# STM32Schemetics.net
KiCad netlist of a schematic drawn in Altium Designer
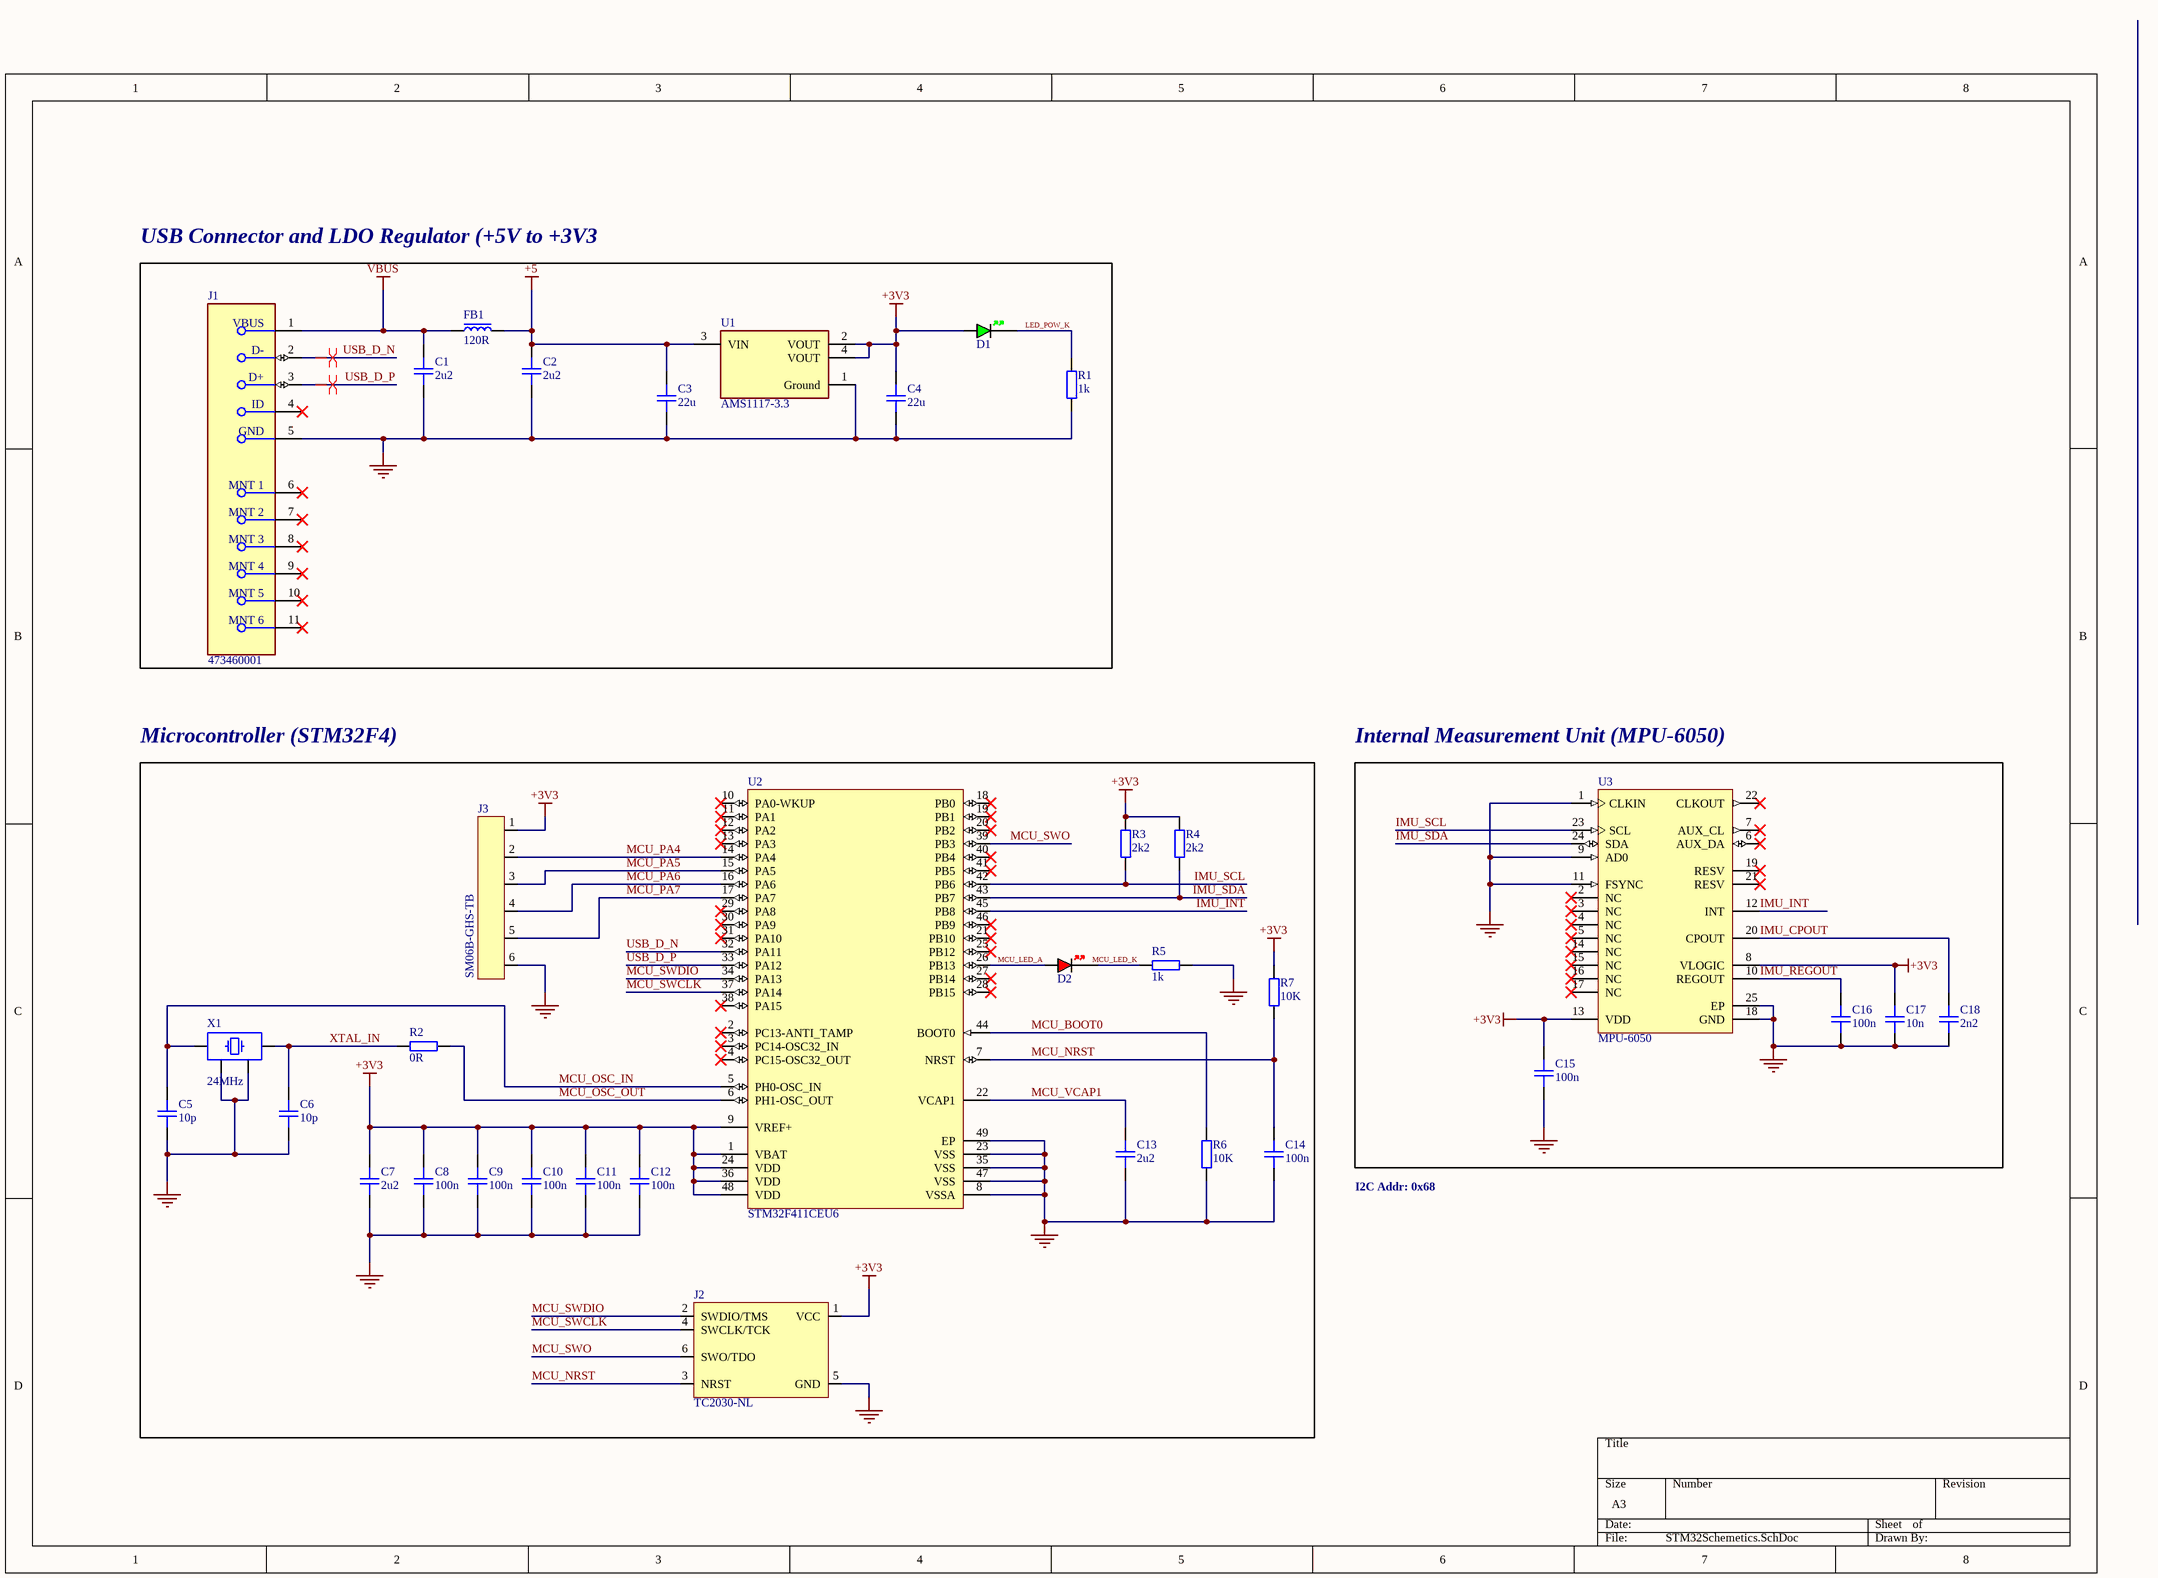
[diagram p0: STM32Schemetics.SchDoc]

(export (version "E")
  (design (tool "Eeschema 10.0.6"))
  (components
    (comp (ref "C1")
      (value "2u2")
      (footprint "CAP_0402")
      (description "Capacitor SMD 0402")
      (libsource (lib "Schematic-Lib-PhilsLab") (part "CAP_0402"))
    )
    (comp (ref "C2")
      (value "2u2")
      (footprint "CAP_0402")
      (description "Capacitor SMD 0402")
      (libsource (lib "Schematic-Lib-PhilsLab") (part "CAP_0402"))
    )
    (comp (ref "C3")
      (value "22u")
      (footprint "CAP_0805")
      (description "Capacitor SMD 0805")
      (libsource (lib "Schematic-Lib-PhilsLab") (part "CAP_0805"))
    )
    (comp (ref "C4")
      (value "22u")
      (footprint "CAP_0805")
      (description "Capacitor SMD 0805")
      (libsource (lib "Schematic-Lib-PhilsLab") (part "CAP_0805"))
    )
    (comp (ref "C5")
      (value "10p")
      (footprint "CAP_0402")
      (description "Capacitor SMD 0402")
      (libsource (lib "Schematic-Lib-PhilsLab") (part "CAP_0402"))
    )
    (comp (ref "C6")
      (value "10p")
      (footprint "CAP_0402")
      (description "Capacitor SMD 0402")
      (libsource (lib "Schematic-Lib-PhilsLab") (part "CAP_0402"))
    )
    (comp (ref "C7")
      (value "2u2")
      (footprint "CAP_0603")
      (description "Capacitor SMD 0603")
      (libsource (lib "Schematic-Lib-PhilsLab") (part "CAP_0603"))
    )
    (comp (ref "C8")
      (value "100n")
      (footprint "CAP_0402")
      (description "Capacitor SMD 0402")
      (libsource (lib "Schematic-Lib-PhilsLab") (part "CAP_0402"))
    )
    (comp (ref "C9")
      (value "100n")
      (footprint "CAP_0402")
      (description "Capacitor SMD 0402")
      (libsource (lib "Schematic-Lib-PhilsLab") (part "CAP_0402"))
    )
    (comp (ref "C10")
      (value "100n")
      (footprint "CAP_0402")
      (description "Capacitor SMD 0402")
      (libsource (lib "Schematic-Lib-PhilsLab") (part "CAP_0402"))
    )
    (comp (ref "C11")
      (value "100n")
      (footprint "CAP_0402")
      (description "Capacitor SMD 0402")
      (libsource (lib "Schematic-Lib-PhilsLab") (part "CAP_0402"))
    )
    (comp (ref "C12")
      (value "100n")
      (footprint "CAP_0402")
      (description "Capacitor SMD 0402")
      (libsource (lib "Schematic-Lib-PhilsLab") (part "CAP_0402"))
    )
    (comp (ref "C13")
      (value "2u2")
      (footprint "CAP_0603")
      (description "Capacitor SMD 0603")
      (libsource (lib "Schematic-Lib-PhilsLab") (part "CAP_0603"))
    )
    (comp (ref "C14")
      (value "100n")
      (footprint "CAP_0402")
      (description "Capacitor SMD 0402")
      (libsource (lib "Schematic-Lib-PhilsLab") (part "CAP_0402"))
    )
    (comp (ref "C15")
      (value "100n")
      (footprint "CAP_0402")
      (description "Capacitor SMD 0402")
      (libsource (lib "Schematic-Lib-PhilsLab") (part "CAP_0402"))
    )
    (comp (ref "C16")
      (value "100n")
      (footprint "CAP_0402")
      (description "Capacitor SMD 0402")
      (libsource (lib "Schematic-Lib-PhilsLab") (part "CAP_0402"))
    )
    (comp (ref "C17")
      (value "10n")
      (footprint "CAP_0402")
      (description "Capacitor SMD 0402")
      (libsource (lib "Schematic-Lib-PhilsLab") (part "CAP_0402"))
    )
    (comp (ref "C18")
      (value "2n2")
      (footprint "CAP_0402")
      (description "Capacitor SMD 0402")
      (libsource (lib "Schematic-Lib-PhilsLab") (part "CAP_0402"))
    )
    (comp (ref "D1")
      (value "GREEN")
      (footprint "LED_0402_GREEN")
      (description "LED 0402 GREEN SMD")
      (libsource (lib "Schematic-Lib-PhilsLab") (part "LED_0402_GREEN"))
    )
    (comp (ref "D2")
      (value "RED")
      (footprint "LED_0402_RED")
      (description "LED 0402 RED SMD")
      (libsource (lib "Schematic-Lib-PhilsLab") (part "LED_0402_RED"))
    )
    (comp (ref "FB1")
      (value "120R")
      (footprint "FB_0603")
      (description "Ferrite Bead SMD 0603")
      (libsource (lib "Schematic-Lib-PhilsLab") (part "FB_0603"))
    )
    (comp (ref "J1")
      (value "473460001")
      (footprint "FP-473460001-MFG")
      (description "CONN RCPT USB2.0 MICRO B SMD R/A")
      (fields
        (field (name "OCTOPART") "https://octopart.com/47346-0001-molex-7164928")
        (field (name "MANUFACTURER") "Molex")
      )
      (libsource (lib "Altium Content Vault") (part "53ae1f1d9b557310b43ca686e5bb76a"))
    )
    (comp (ref "J2")
      (value "TC2030-NL")
      (footprint "TC2030-NL-FP")
      (description "Tag-Connect No-Solder SWD Debug Connector (No Legs) DO NOT PLACE")
      (fields
        (field (name "MANUFACTURER") "Tag-Connect")
        (field (name "MANUFACTURER PART NUMBER") "TC2030-NL-FP")
      )
      (libsource (lib "Schematic-Lib-PhilsLab") (part "TC2030-NL"))
    )
    (comp (ref "J3")
      (value "SM06B-GHS-TB")
      (footprint "SM06B-GHS-TB")
      (description "Header Connector 6 Position 1.25MM Pitch SMD Horizontal JST GH")
      (fields (field (name "MANUFACTURER") "JST"))
      (libsource (lib "Schematic-Lib-PhilsLab") (part "SM06B-GHS-TB"))
    )
    (comp (ref "R1")
      (value "1k")
      (footprint "RES_0402")
      (description "Resistor SMD 0402")
      (libsource (lib "Schematic-Lib-PhilsLab") (part "RES_0402"))
    )
    (comp (ref "R2")
      (value "0R")
      (footprint "RES_0402")
      (description "Resistor SMD 0402")
      (libsource (lib "Schematic-Lib-PhilsLab") (part "RES_0402"))
    )
    (comp (ref "R3")
      (value "2k2")
      (footprint "RES_0402")
      (description "Resistor SMD 0402")
      (libsource (lib "Schematic-Lib-PhilsLab") (part "RES_0402"))
    )
    (comp (ref "R4")
      (value "2k2")
      (footprint "RES_0402")
      (description "Resistor SMD 0402")
      (libsource (lib "Schematic-Lib-PhilsLab") (part "RES_0402"))
    )
    (comp (ref "R5")
      (value "1k")
      (footprint "RES_0402")
      (description "Resistor SMD 0402")
      (libsource (lib "Schematic-Lib-PhilsLab") (part "RES_0402"))
    )
    (comp (ref "R6")
      (value "10K")
      (footprint "RES_0402")
      (description "Resistor SMD 0402")
      (libsource (lib "Schematic-Lib-PhilsLab") (part "RES_0402"))
    )
    (comp (ref "R7")
      (value "10K")
      (footprint "RES_0402")
      (description "Resistor SMD 0402")
      (libsource (lib "Schematic-Lib-PhilsLab") (part "RES_0402"))
    )
    (comp (ref "U1")
      (value "AMS1117-3.3")
      (footprint "FP-AMS1117-IPC_C")
      (description "LDO Voltage Regulators 1A, 3.3V")
      (fields
        (field (name "OCTOPART") "https://octopart.com/ams1117-3.3-advanced+monolithic+systems-25899300")
        (field (name "MANUFACTURER") "Advanced Monolithic Systems")
      )
      (libsource (lib "Altium Content Vault") (part "8bdbb5f8e77002000e30dd2845d0354"))
    )
    (comp (ref "U2")
      (value "STM32F411CEU6")
      (footprint "STM-UFQFPN48_L")
      (libsource (lib "Altium Content Vault") (part "MC-ARM-STM32F411-UFQFPN48"))
    )
    (comp (ref "U3")
      (value "MPU-6050")
      (footprint "IS-QFN-24_V")
      (fields (field (name "MANUFACTURER") "InvenSense"))
      (libsource (lib "Altium Content Vault") (part "IS-MPU-6050-QFN-24"))
    )
    (comp (ref "X1")
      (value "24MHz")
      (footprint "XTAL_3225")
      (description "Crystal SMD 24MHz 10PPM 7pF 3225")
      (fields
        (field (name "MANUFACTURER") "Epson")
        (field (name "MANUFACTURER PART NUMBER") "TSX-3225 24.0000MF15X-AC")
      )
      (libsource (lib "Schematic-Lib-PhilsLab") (part "TSX-3225_24.0000MF15X-AC"))
    )
  )
  (nets
    (net (code "1") (name "+3V3") (class "Default")
      (node (ref "C10") (pin "2") (pinfunction "2_2") (pintype "passive"))
      (node (ref "C11") (pin "2") (pinfunction "2_2") (pintype "passive"))
      (node (ref "C12") (pin "2") (pinfunction "2_2") (pintype "passive"))
      (node (ref "C15") (pin "2") (pinfunction "2_2") (pintype "passive"))
      (node (ref "C17") (pin "2") (pinfunction "2_2") (pintype "passive"))
      (node (ref "C4") (pin "2") (pinfunction "2_2") (pintype "passive"))
      (node (ref "C7") (pin "2") (pinfunction "2_2") (pintype "passive"))
      (node (ref "C8") (pin "2") (pinfunction "2_2") (pintype "passive"))
      (node (ref "C9") (pin "2") (pinfunction "2_2") (pintype "passive"))
      (node (ref "D1") (pin "A") (pinfunction "A_A") (pintype "passive"))
      (node (ref "J2") (pin "1") (pinfunction "VCC_1") (pintype "passive"))
      (node (ref "J3") (pin "1") (pinfunction "1_1") (pintype "passive"))
      (node (ref "R3") (pin "2") (pinfunction "2_2") (pintype "passive"))
      (node (ref "R4") (pin "2") (pinfunction "2_2") (pintype "passive"))
      (node (ref "R7") (pin "2") (pinfunction "2_2") (pintype "passive"))
      (node (ref "U1") (pin "2") (pinfunction "VOUT_2") (pintype "passive"))
      (node (ref "U1") (pin "4") (pinfunction "VOUT_4") (pintype "passive"))
      (node (ref "U2") (pin "1") (pinfunction "VBAT_1") (pintype "power_in"))
      (node (ref "U2") (pin "24") (pinfunction "VDD_24") (pintype "power_in"))
      (node (ref "U2") (pin "36") (pinfunction "VDD_36") (pintype "power_in"))
      (node (ref "U2") (pin "48") (pinfunction "VDD_48") (pintype "power_in"))
      (node (ref "U2") (pin "9") (pinfunction "VREF+_9") (pintype "power_in"))
      (node (ref "U3") (pin "13") (pinfunction "VDD_13") (pintype "power_in"))
      (node (ref "U3") (pin "8") (pinfunction "VLOGIC_8") (pintype "power_in"))
    )
    (net (code "2") (name "+5") (class "Default")
      (node (ref "C2") (pin "2") (pinfunction "2_2") (pintype "passive"))
      (node (ref "C3") (pin "2") (pinfunction "2_2") (pintype "passive"))
      (node (ref "FB1") (pin "2") (pinfunction "2_2") (pintype "passive"))
      (node (ref "U1") (pin "3") (pinfunction "VIN_3") (pintype "power_in"))
    )
    (net (code "3") (name "/IMU_CPOUT") (class "Default")
      (node (ref "C18") (pin "2") (pinfunction "2_2") (pintype "passive"))
      (node (ref "U3") (pin "20") (pinfunction "CPOUT_20") (pintype "passive"))
    )
    (net (code "4") (name "/IMU_INT") (class "Default")
      (node (ref "U2") (pin "45") (pinfunction "PB8_45") (pintype "bidirectional"))
      (node (ref "U3") (pin "12") (pinfunction "INT_12") (pintype "open_collector"))
    )
    (net (code "5") (name "/IMU_REGOUT") (class "Default")
      (node (ref "C16") (pin "2") (pinfunction "2_2") (pintype "passive"))
      (node (ref "U3") (pin "10") (pinfunction "REGOUT_10") (pintype "passive"))
    )
    (net (code "6") (name "/IMU_SCL") (class "Default")
      (node (ref "R3") (pin "1") (pinfunction "1_1") (pintype "passive"))
      (node (ref "U2") (pin "42") (pinfunction "PB6_42") (pintype "bidirectional"))
      (node (ref "U3") (pin "23") (pinfunction "SCL_23") (pintype "input"))
    )
    (net (code "7") (name "/IMU_SDA") (class "Default")
      (node (ref "R4") (pin "1") (pinfunction "1_1") (pintype "passive"))
      (node (ref "U2") (pin "43") (pinfunction "PB7_43") (pintype "bidirectional"))
      (node (ref "U3") (pin "24") (pinfunction "SDA_24") (pintype "bidirectional"))
    )
    (net (code "8") (name "/LED_POW_K") (class "Default")
      (node (ref "D1") (pin "K") (pinfunction "K_K") (pintype "passive"))
      (node (ref "R1") (pin "2") (pinfunction "2_2") (pintype "passive"))
    )
    (net (code "9") (name "/MCU_BOOT0") (class "Default")
      (node (ref "R6") (pin "2") (pinfunction "2_2") (pintype "passive"))
      (node (ref "U2") (pin "44") (pinfunction "BOOT0_44") (pintype "input"))
    )
    (net (code "10") (name "/MCU_LED_A") (class "Default")
      (node (ref "D2") (pin "A") (pinfunction "A_A") (pintype "passive"))
      (node (ref "U2") (pin "26") (pinfunction "PB13_26") (pintype "bidirectional"))
    )
    (net (code "11") (name "/MCU_LED_K") (class "Default")
      (node (ref "D2") (pin "K") (pinfunction "K_K") (pintype "passive"))
      (node (ref "R5") (pin "2") (pinfunction "2_2") (pintype "passive"))
    )
    (net (code "12") (name "/MCU_NRST") (class "Default")
      (node (ref "C14") (pin "2") (pinfunction "2_2") (pintype "passive"))
      (node (ref "J2") (pin "3") (pinfunction "NRST_3") (pintype "passive"))
      (node (ref "R7") (pin "1") (pinfunction "1_1") (pintype "passive"))
      (node (ref "U2") (pin "7") (pinfunction "NRST_7") (pintype "bidirectional"))
    )
    (net (code "13") (name "/MCU_OSC_IN") (class "Default")
      (node (ref "C5") (pin "2") (pinfunction "2_2") (pintype "passive"))
      (node (ref "U2") (pin "5") (pinfunction "PH0-OSC_IN_5") (pintype "bidirectional"))
      (node (ref "X1") (pin "1") (pinfunction "1_1") (pintype "passive"))
    )
    (net (code "14") (name "/MCU_OSC_OUT") (class "Default")
      (node (ref "R2") (pin "1") (pinfunction "1_1") (pintype "passive"))
      (node (ref "U2") (pin "6") (pinfunction "PH1-OSC_OUT_6") (pintype "bidirectional"))
    )
    (net (code "15") (name "/MCU_PA4") (class "Default")
      (node (ref "J3") (pin "2") (pinfunction "2_2") (pintype "passive"))
      (node (ref "U2") (pin "14") (pinfunction "PA4_14") (pintype "bidirectional"))
    )
    (net (code "16") (name "/MCU_PA5") (class "Default")
      (node (ref "J3") (pin "3") (pinfunction "3_3") (pintype "passive"))
      (node (ref "U2") (pin "15") (pinfunction "PA5_15") (pintype "bidirectional"))
    )
    (net (code "17") (name "/MCU_PA6") (class "Default")
      (node (ref "J3") (pin "4") (pinfunction "4_4") (pintype "passive"))
      (node (ref "U2") (pin "16") (pinfunction "PA6_16") (pintype "bidirectional"))
    )
    (net (code "18") (name "/MCU_PA7") (class "Default")
      (node (ref "J3") (pin "5") (pinfunction "5_5") (pintype "passive"))
      (node (ref "U2") (pin "17") (pinfunction "PA7_17") (pintype "bidirectional"))
    )
    (net (code "19") (name "/MCU_SWCLK") (class "Default")
      (node (ref "J2") (pin "4") (pinfunction "SWCLK/TCK_4") (pintype "passive"))
      (node (ref "U2") (pin "37") (pinfunction "PA14_37") (pintype "bidirectional"))
    )
    (net (code "20") (name "/MCU_SWDIO") (class "Default")
      (node (ref "J2") (pin "2") (pinfunction "SWDIO/TMS_2") (pintype "passive"))
      (node (ref "U2") (pin "34") (pinfunction "PA13_34") (pintype "bidirectional"))
    )
    (net (code "21") (name "/MCU_SWO") (class "Default")
      (node (ref "J2") (pin "6") (pinfunction "SWO/TDO_6") (pintype "passive"))
      (node (ref "U2") (pin "39") (pinfunction "PB3_39") (pintype "bidirectional"))
    )
    (net (code "22") (name "/MCU_VCAP1") (class "Default")
      (node (ref "C13") (pin "2") (pinfunction "2_2") (pintype "passive"))
      (node (ref "U2") (pin "22") (pinfunction "VCAP1_22") (pintype "passive"))
    )
    (net (code "23") (name "/USB_D_N") (class "Default")
      (node (ref "J1") (pin "2") (pinfunction "D-_2") (pintype "bidirectional"))
      (node (ref "U2") (pin "32") (pinfunction "PA11_32") (pintype "bidirectional"))
    )
    (net (code "24") (name "/USB_D_P") (class "Default")
      (node (ref "J1") (pin "3") (pinfunction "D+_3") (pintype "bidirectional"))
      (node (ref "U2") (pin "33") (pinfunction "PA12_33") (pintype "bidirectional"))
    )
    (net (code "25") (name "/XTAL_IN") (class "Default")
      (node (ref "C6") (pin "2") (pinfunction "2_2") (pintype "passive"))
      (node (ref "R2") (pin "2") (pinfunction "2_2") (pintype "passive"))
      (node (ref "X1") (pin "3") (pinfunction "3_3") (pintype "passive"))
    )
    (net (code "26") (name "GND") (class "Default")
      (node (ref "C1") (pin "1") (pinfunction "1_1") (pintype "passive"))
      (node (ref "C10") (pin "1") (pinfunction "1_1") (pintype "passive"))
      (node (ref "C11") (pin "1") (pinfunction "1_1") (pintype "passive"))
      (node (ref "C12") (pin "1") (pinfunction "1_1") (pintype "passive"))
      (node (ref "C13") (pin "1") (pinfunction "1_1") (pintype "passive"))
      (node (ref "C14") (pin "1") (pinfunction "1_1") (pintype "passive"))
      (node (ref "C15") (pin "1") (pinfunction "1_1") (pintype "passive"))
      (node (ref "C16") (pin "1") (pinfunction "1_1") (pintype "passive"))
      (node (ref "C17") (pin "1") (pinfunction "1_1") (pintype "passive"))
      (node (ref "C18") (pin "1") (pinfunction "1_1") (pintype "passive"))
      (node (ref "C2") (pin "1") (pinfunction "1_1") (pintype "passive"))
      (node (ref "C3") (pin "1") (pinfunction "1_1") (pintype "passive"))
      (node (ref "C4") (pin "1") (pinfunction "1_1") (pintype "passive"))
      (node (ref "C5") (pin "1") (pinfunction "1_1") (pintype "passive"))
      (node (ref "C6") (pin "1") (pinfunction "1_1") (pintype "passive"))
      (node (ref "C7") (pin "1") (pinfunction "1_1") (pintype "passive"))
      (node (ref "C8") (pin "1") (pinfunction "1_1") (pintype "passive"))
      (node (ref "C9") (pin "1") (pinfunction "1_1") (pintype "passive"))
      (node (ref "J1") (pin "5") (pinfunction "GND_5") (pintype "power_in"))
      (node (ref "J2") (pin "5") (pinfunction "GND_5") (pintype "passive"))
      (node (ref "J3") (pin "6") (pinfunction "6_6") (pintype "passive"))
      (node (ref "R1") (pin "1") (pinfunction "1_1") (pintype "passive"))
      (node (ref "R5") (pin "1") (pinfunction "1_1") (pintype "passive"))
      (node (ref "R6") (pin "1") (pinfunction "1_1") (pintype "passive"))
      (node (ref "U1") (pin "1") (pinfunction "Ground_1") (pintype "power_in"))
      (node (ref "U2") (pin "23") (pinfunction "VSS_23") (pintype "power_in"))
      (node (ref "U2") (pin "35") (pinfunction "VSS_35") (pintype "power_in"))
      (node (ref "U2") (pin "47") (pinfunction "VSS_47") (pintype "power_in"))
      (node (ref "U2") (pin "49") (pinfunction "EP_49") (pintype "power_in"))
      (node (ref "U2") (pin "8") (pinfunction "VSSA_8") (pintype "power_in"))
      (node (ref "U3") (pin "1") (pinfunction "CLKIN_1") (pintype "input"))
      (node (ref "U3") (pin "11") (pinfunction "FSYNC_11") (pintype "input"))
      (node (ref "U3") (pin "18") (pinfunction "GND_18") (pintype "power_in"))
      (node (ref "U3") (pin "25") (pinfunction "EP_25") (pintype "power_in"))
      (node (ref "U3") (pin "9") (pinfunction "AD0_9") (pintype "input"))
      (node (ref "X1") (pin "2") (pinfunction "2_2") (pintype "passive"))
      (node (ref "X1") (pin "4") (pinfunction "4_4") (pintype "passive"))
    )
    (net (code "27") (name "VBUS") (class "Default")
      (node (ref "C1") (pin "2") (pinfunction "2_2") (pintype "passive"))
      (node (ref "FB1") (pin "1") (pinfunction "1_1") (pintype "passive"))
      (node (ref "J1") (pin "1") (pinfunction "VBUS_1") (pintype "power_in"))
    )
    (net (code "28") (name "unconnected-(J1-ID-Pad4)") (class "Default")
      (node (ref "J1") (pin "4") (pinfunction "ID_4") (pintype "passive+no_connect"))
    )
    (net (code "29") (name "unconnected-(J1-MNT_1-Pad6)") (class "Default")
      (node (ref "J1") (pin "6") (pinfunction "MNT_1_6") (pintype "passive+no_connect"))
    )
    (net (code "30") (name "unconnected-(J1-MNT_2-Pad7)") (class "Default")
      (node (ref "J1") (pin "7") (pinfunction "MNT_2_7") (pintype "passive+no_connect"))
    )
    (net (code "31") (name "unconnected-(J1-MNT_3-Pad8)") (class "Default")
      (node (ref "J1") (pin "8") (pinfunction "MNT_3_8") (pintype "passive+no_connect"))
    )
    (net (code "32") (name "unconnected-(J1-MNT_4-Pad9)") (class "Default")
      (node (ref "J1") (pin "9") (pinfunction "MNT_4_9") (pintype "passive+no_connect"))
    )
    (net (code "33") (name "unconnected-(J1-MNT_5-Pad10)") (class "Default")
      (node (ref "J1") (pin "10") (pinfunction "MNT_5_10") (pintype "passive+no_connect"))
    )
    (net (code "34") (name "unconnected-(J1-MNT_6-Pad11)") (class "Default")
      (node (ref "J1") (pin "11") (pinfunction "MNT_6_11") (pintype "passive+no_connect"))
    )
    (net (code "35") (name "unconnected-(U2-PA0-WKUP-Pad10)") (class "Default")
      (node (ref "U2") (pin "10") (pinfunction "PA0-WKUP_10") (pintype "bidirectional+no_connect"))
    )
    (net (code "36") (name "unconnected-(U2-PA1-Pad11)") (class "Default")
      (node (ref "U2") (pin "11") (pinfunction "PA1_11") (pintype "bidirectional+no_connect"))
    )
    (net (code "37") (name "unconnected-(U2-PA2-Pad12)") (class "Default")
      (node (ref "U2") (pin "12") (pinfunction "PA2_12") (pintype "bidirectional+no_connect"))
    )
    (net (code "38") (name "unconnected-(U2-PA3-Pad13)") (class "Default")
      (node (ref "U2") (pin "13") (pinfunction "PA3_13") (pintype "bidirectional+no_connect"))
    )
    (net (code "39") (name "unconnected-(U2-PA8-Pad29)") (class "Default")
      (node (ref "U2") (pin "29") (pinfunction "PA8_29") (pintype "bidirectional+no_connect"))
    )
    (net (code "40") (name "unconnected-(U2-PA9-Pad30)") (class "Default")
      (node (ref "U2") (pin "30") (pinfunction "PA9_30") (pintype "bidirectional+no_connect"))
    )
    (net (code "41") (name "unconnected-(U2-PA10-Pad31)") (class "Default")
      (node (ref "U2") (pin "31") (pinfunction "PA10_31") (pintype "bidirectional+no_connect"))
    )
    (net (code "42") (name "unconnected-(U2-PA15-Pad38)") (class "Default")
      (node (ref "U2") (pin "38") (pinfunction "PA15_38") (pintype "bidirectional+no_connect"))
    )
    (net (code "43") (name "unconnected-(U2-PB0-Pad18)") (class "Default")
      (node (ref "U2") (pin "18") (pinfunction "PB0_18") (pintype "bidirectional+no_connect"))
    )
    (net (code "44") (name "unconnected-(U2-PB1-Pad19)") (class "Default")
      (node (ref "U2") (pin "19") (pinfunction "PB1_19") (pintype "bidirectional+no_connect"))
    )
    (net (code "45") (name "unconnected-(U2-PB2-Pad20)") (class "Default")
      (node (ref "U2") (pin "20") (pinfunction "PB2_20") (pintype "bidirectional+no_connect"))
    )
    (net (code "46") (name "unconnected-(U2-PB4-Pad40)") (class "Default")
      (node (ref "U2") (pin "40") (pinfunction "PB4_40") (pintype "bidirectional+no_connect"))
    )
    (net (code "47") (name "unconnected-(U2-PB5-Pad41)") (class "Default")
      (node (ref "U2") (pin "41") (pinfunction "PB5_41") (pintype "bidirectional+no_connect"))
    )
    (net (code "48") (name "unconnected-(U2-PB9-Pad46)") (class "Default")
      (node (ref "U2") (pin "46") (pinfunction "PB9_46") (pintype "bidirectional+no_connect"))
    )
    (net (code "49") (name "unconnected-(U2-PB10-Pad21)") (class "Default")
      (node (ref "U2") (pin "21") (pinfunction "PB10_21") (pintype "bidirectional+no_connect"))
    )
    (net (code "50") (name "unconnected-(U2-PB12-Pad25)") (class "Default")
      (node (ref "U2") (pin "25") (pinfunction "PB12_25") (pintype "bidirectional+no_connect"))
    )
    (net (code "51") (name "unconnected-(U2-PB14-Pad27)") (class "Default")
      (node (ref "U2") (pin "27") (pinfunction "PB14_27") (pintype "bidirectional+no_connect"))
    )
    (net (code "52") (name "unconnected-(U2-PB15-Pad28)") (class "Default")
      (node (ref "U2") (pin "28") (pinfunction "PB15_28") (pintype "bidirectional+no_connect"))
    )
    (net (code "53") (name "unconnected-(U2-PC13-ANTI_TAMP-Pad2)") (class "Default")
      (node (ref "U2") (pin "2") (pinfunction "PC13-ANTI_TAMP_2") (pintype "bidirectional+no_connect"))
    )
    (net (code "54") (name "unconnected-(U2-PC14-OSC32_IN-Pad3)") (class "Default")
      (node (ref "U2") (pin "3") (pinfunction "PC14-OSC32_IN_3") (pintype "bidirectional+no_connect"))
    )
    (net (code "55") (name "unconnected-(U2-PC15-OSC32_OUT-Pad4)") (class "Default")
      (node (ref "U2") (pin "4") (pinfunction "PC15-OSC32_OUT_4") (pintype "bidirectional+no_connect"))
    )
    (net (code "56") (name "unconnected-(U3-AUX_CL-Pad7)") (class "Default")
      (node (ref "U3") (pin "7") (pinfunction "AUX_CL_7") (pintype "output+no_connect"))
    )
    (net (code "57") (name "unconnected-(U3-AUX_DA-Pad6)") (class "Default")
      (node (ref "U3") (pin "6") (pinfunction "AUX_DA_6") (pintype "bidirectional+no_connect"))
    )
    (net (code "58") (name "unconnected-(U3-CLKOUT-Pad22)") (class "Default")
      (node (ref "U3") (pin "22") (pinfunction "CLKOUT_22") (pintype "output+no_connect"))
    )
    (net (code "59") (name "unconnected-(U3-NC-Pad2)") (class "Default")
      (node (ref "U3") (pin "2") (pinfunction "NC_2") (pintype "passive+no_connect"))
    )
    (net (code "60") (name "unconnected-(U3-NC-Pad3)") (class "Default")
      (node (ref "U3") (pin "3") (pinfunction "NC_3") (pintype "passive+no_connect"))
    )
    (net (code "61") (name "unconnected-(U3-NC-Pad4)") (class "Default")
      (node (ref "U3") (pin "4") (pinfunction "NC_4") (pintype "passive+no_connect"))
    )
    (net (code "62") (name "unconnected-(U3-NC-Pad5)") (class "Default")
      (node (ref "U3") (pin "5") (pinfunction "NC_5") (pintype "passive+no_connect"))
    )
    (net (code "63") (name "unconnected-(U3-NC-Pad14)") (class "Default")
      (node (ref "U3") (pin "14") (pinfunction "NC_14") (pintype "passive+no_connect"))
    )
    (net (code "64") (name "unconnected-(U3-NC-Pad15)") (class "Default")
      (node (ref "U3") (pin "15") (pinfunction "NC_15") (pintype "passive+no_connect"))
    )
    (net (code "65") (name "unconnected-(U3-NC-Pad16)") (class "Default")
      (node (ref "U3") (pin "16") (pinfunction "NC_16") (pintype "passive+no_connect"))
    )
    (net (code "66") (name "unconnected-(U3-NC-Pad17)") (class "Default")
      (node (ref "U3") (pin "17") (pinfunction "NC_17") (pintype "passive+no_connect"))
    )
    (net (code "67") (name "unconnected-(U3-RESV-Pad19)") (class "Default")
      (node (ref "U3") (pin "19") (pinfunction "RESV_19") (pintype "passive+no_connect"))
    )
    (net (code "68") (name "unconnected-(U3-RESV-Pad21)") (class "Default")
      (node (ref "U3") (pin "21") (pinfunction "RESV_21") (pintype "passive+no_connect"))
    )
  )
)
